# LightBox.net
KiCad netlist of a schematic drawn in Altium Designer
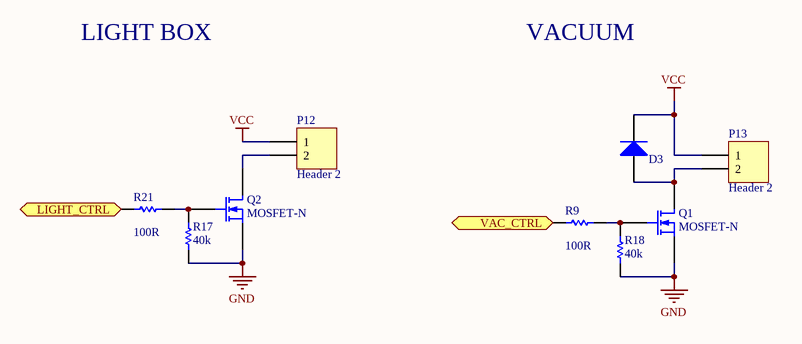
[diagram p0: LightBox.SchDoc]

(export (version "E")
  (design (tool "Eeschema 10.0.6"))
  (components
    (comp (ref "D3")
      (value "Diode MMBD914")
      (footprint "SOT-23")
      (description "Standard Diode")
      (fields
        (field (name "DIGI-KEY PART NO.") "MMBD914LT1GOSCT-ND")
        (field (name "MANUFACTURER PART NO.") "MMBD914LT1G")
      )
      (libsource (lib "Semiconductors") (part "Diode MMBD914"))
    )
    (comp (ref "P12")
      (value "Header 2")
      (footprint "HDR1X2")
      (description "Header, 2-Pin")
      (fields (field (name "PUBLISHER") "Altium Limited"))
      (libsource (lib "Miscellaneous Connectors") (part "Header 2"))
    )
    (comp (ref "P13")
      (value "Header 2")
      (footprint "HDR1X2")
      (description "Header, 2-Pin")
      (fields (field (name "PUBLISHER") "Altium Limited"))
      (libsource (lib "Miscellaneous Connectors") (part "Header 2"))
    )
    (comp (ref "Q1")
      (value "MOSFET-N")
      (footprint "DPAK")
      (description "N-Channel MOSFET")
      (fields
        (field (name "DIGI-KEY PART NO.") "497-2477-1-ND")
        (field (name "MANUFACTURER PART NO.") "STD5NK40ZT4")
      )
      (libsource (lib "Semiconductors") (part "N-Channel MOSFET"))
    )
    (comp (ref "Q2")
      (value "MOSFET-N")
      (footprint "DPAK")
      (description "N-Channel MOSFET")
      (fields
        (field (name "DIGI-KEY PART NO.") "497-2477-1-ND")
        (field (name "MANUFACTURER PART NO.") "STD5NK40ZT4")
      )
      (libsource (lib "Semiconductors") (part "N-Channel MOSFET"))
    )
    (comp (ref "R9")
      (value "100R")
      (footprint "0805")
      (description "Resistor")
      (fields (field (name "Comment") "Res1") (field (name "PUBLISHER") "Altium Limited"))
      (libsource (lib "Miscellaneous Devices") (part "Res1"))
    )
    (comp (ref "R17")
      (value "40k")
      (footprint "0805")
      (description "Chip Resistor")
      (fields (field (name "Comment") "Resistor"))
      (libsource (lib "RCL") (part "Resistor"))
    )
    (comp (ref "R18")
      (value "40k")
      (footprint "0805")
      (description "Chip Resistor")
      (fields (field (name "Comment") "Resistor"))
      (libsource (lib "RCL") (part "Resistor"))
    )
    (comp (ref "R21")
      (value "100R")
      (footprint "0805")
      (description "Resistor")
      (fields (field (name "Comment") "Res1") (field (name "PUBLISHER") "Altium Limited"))
      (libsource (lib "Miscellaneous Devices") (part "Res1"))
    )
  )
  (nets
    (net (code "1") (name "/LIGHT_CTRL") (class "Default")
      (node (ref "R21") (pin "1") (pinfunction "1_1") (pintype "passive"))
    )
    (net (code "2") (name "/VAC_CTRL") (class "Default")
      (node (ref "R9") (pin "1") (pinfunction "1_1") (pintype "passive"))
    )
    (net (code "3") (name "GND") (class "Default")
      (node (ref "Q1") (pin "3") (pinfunction "S_3") (pintype "passive"))
      (node (ref "Q2") (pin "3") (pinfunction "S_3") (pintype "passive"))
      (node (ref "R17") (pin "1") (pinfunction "1_1") (pintype "passive"))
      (node (ref "R18") (pin "1") (pinfunction "1_1") (pintype "passive"))
    )
    (net (code "4") (name "Net-(D3-A)") (class "Default")
      (node (ref "D3") (pin "1") (pinfunction "A_1") (pintype "passive"))
      (node (ref "P13") (pin "2") (pinfunction "2_2") (pintype "passive"))
      (node (ref "Q1") (pin "2") (pinfunction "D_2") (pintype "passive"))
    )
    (net (code "5") (name "Net-(Q1-G)") (class "Default")
      (node (ref "Q1") (pin "1") (pinfunction "G_1") (pintype "passive"))
      (node (ref "R18") (pin "2") (pinfunction "2_2") (pintype "passive"))
      (node (ref "R9") (pin "2") (pinfunction "2_2") (pintype "passive"))
    )
    (net (code "6") (name "Net-(Q2-D)") (class "Default")
      (node (ref "P12") (pin "2") (pinfunction "2_2") (pintype "passive"))
      (node (ref "Q2") (pin "2") (pinfunction "D_2") (pintype "passive"))
    )
    (net (code "7") (name "Net-(Q2-G)") (class "Default")
      (node (ref "Q2") (pin "1") (pinfunction "G_1") (pintype "passive"))
      (node (ref "R17") (pin "2") (pinfunction "2_2") (pintype "passive"))
      (node (ref "R21") (pin "2") (pinfunction "2_2") (pintype "passive"))
    )
    (net (code "8") (name "VCC") (class "Default")
      (node (ref "D3") (pin "3") (pinfunction "K_3") (pintype "passive"))
      (node (ref "P12") (pin "1") (pinfunction "1_1") (pintype "passive"))
      (node (ref "P13") (pin "1") (pinfunction "1_1") (pintype "passive"))
    )
  )
)
